# TopLevel.net
KiCad netlist of a schematic drawn in Altium Designer
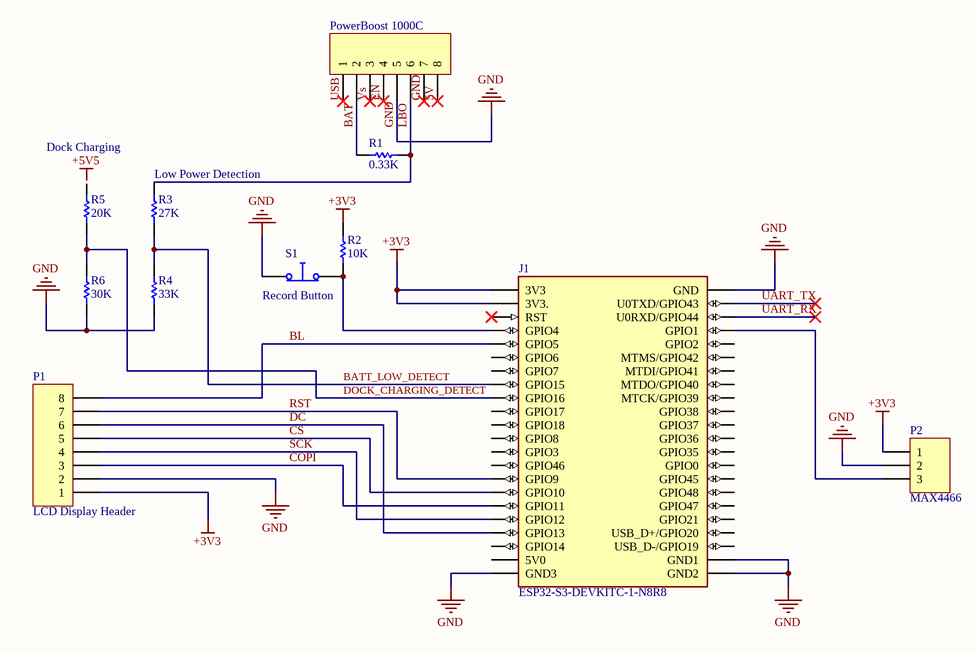
[diagram p0: TopLevel.SchDoc]

(export (version "E")
  (design (tool "Eeschema 10.0.6"))
  (components
    (comp (ref "J1")
      (value "ESP32-S3-DEVKITC-1-N8R8")
      (footprint "ESP32-S3-DEVKITC-1-N8R8")
      (fields (field (name "MF") "Espressif Systems"))
      (libsource (lib "Personal") (part "ESP32-S3-DEVKITC-1-N8R8"))
    )
    (comp (ref "P1")
      (value "LCD Display Header")
      (footprint "HDR1X8")
      (description "Header, 8-Pin")
      (fields (field (name "PUBLISHER") "Altium Limited"))
      (libsource (lib "") (part "Header 8H_1"))
    )
    (comp (ref "P2")
      (value "MAX4466")
      (footprint "HDR1X3")
      (description "Header, 3-Pin")
      (fields (field (name "PUBLISHER") "Altium Limited"))
      (libsource (lib "Personal") (part "Header 3H"))
    )
    (comp (ref "PowerBoost 1000C")
      (value "CD Display Header")
      (footprint "HDR1X8")
      (description "Header, 8-Pin")
      (fields (field (name "PUBLISHER") "Altium Limited"))
      (libsource (lib "Personal") (part "Header 8H"))
    )
    (comp (ref "R1")
      (value "0.33K")
      (description "Resistor")
      (libsource (lib "Simulation Generic Components") (part "Resistor"))
    )
    (comp (ref "R2")
      (value "10K")
      (description "Resistor")
      (libsource (lib "Simulation Generic Components") (part "Resistor"))
    )
    (comp (ref "R3")
      (value "27K")
      (description "Resistor")
      (libsource (lib "Simulation Generic Components") (part "Resistor"))
    )
    (comp (ref "R4")
      (value "33K")
      (description "Resistor")
      (libsource (lib "Simulation Generic Components") (part "Resistor"))
    )
    (comp (ref "R5")
      (value "20K")
      (description "Resistor")
      (libsource (lib "Simulation Generic Components") (part "Resistor"))
    )
    (comp (ref "R6")
      (value "30K")
      (description "Resistor")
      (libsource (lib "Simulation Generic Components") (part "Resistor"))
    )
    (comp (ref "S1")
      (value "Push Button Normally Closed")
      (libsource (lib "Simulation Generic Components") (part "Push Button NC"))
    )
  )
  (nets
    (net (code "1") (name "+3V3") (class "Default")
      (node (ref "J1") (pin "J1_1") (pinfunction "3V3_J1_1") (pintype "power_in"))
      (node (ref "J1") (pin "J1_2") (pinfunction "3V3._J1_2") (pintype "power_in"))
      (node (ref "P1") (pin "1") (pinfunction "1_1") (pintype "passive"))
      (node (ref "P2") (pin "1") (pinfunction "1_1") (pintype "passive"))
      (node (ref "R2") (pin "2") (pinfunction "2_2") (pintype "passive"))
    )
    (net (code "2") (name "+5V5") (class "Default")
      (node (ref "R5") (pin "2") (pinfunction "2_2") (pintype "passive"))
    )
    (net (code "3") (name "/5V") (class "Default")
      (node (ref "PowerBoost 1000C") (pin "8") (pinfunction "8_8") (pintype "passive+no_connect"))
    )
    (net (code "4") (name "/BAT") (class "Default")
      (node (ref "PowerBoost 1000C") (pin "2") (pinfunction "2_2") (pintype "passive"))
      (node (ref "R1") (pin "2") (pinfunction "2_2") (pintype "passive"))
    )
    (net (code "5") (name "/BATT_LOW_DETECT") (class "Default")
      (node (ref "J1") (pin "J1_8") (pinfunction "GPIO15_J1_8") (pintype "bidirectional"))
      (node (ref "R3") (pin "1") (pinfunction "1_1") (pintype "passive"))
      (node (ref "R4") (pin "2") (pinfunction "2_2") (pintype "passive"))
    )
    (net (code "6") (name "/BL") (class "Default")
      (node (ref "J1") (pin "J1_5") (pinfunction "GPIO5_J1_5") (pintype "bidirectional"))
      (node (ref "P1") (pin "8") (pinfunction "8_8") (pintype "passive"))
    )
    (net (code "7") (name "/COPI") (class "Default")
      (node (ref "J1") (pin "J1_17") (pinfunction "GPIO11_J1_17") (pintype "bidirectional"))
      (node (ref "P1") (pin "3") (pinfunction "3_3") (pintype "passive"))
    )
    (net (code "8") (name "/CS") (class "Default")
      (node (ref "J1") (pin "J1_16") (pinfunction "GPIO10_J1_16") (pintype "bidirectional"))
      (node (ref "P1") (pin "5") (pinfunction "5_5") (pintype "passive"))
    )
    (net (code "9") (name "/DC") (class "Default")
      (node (ref "J1") (pin "J1_19") (pinfunction "GPIO13_J1_19") (pintype "bidirectional"))
      (node (ref "P1") (pin "6") (pinfunction "6_6") (pintype "passive"))
    )
    (net (code "10") (name "/DOCK_CHARGING_DETECT") (class "Default")
      (node (ref "J1") (pin "J1_9") (pinfunction "GPIO16_J1_9") (pintype "bidirectional"))
      (node (ref "R5") (pin "1") (pinfunction "1_1") (pintype "passive"))
      (node (ref "R6") (pin "2") (pinfunction "2_2") (pintype "passive"))
    )
    (net (code "11") (name "/EN") (class "Default")
      (node (ref "PowerBoost 1000C") (pin "4") (pinfunction "4_4") (pintype "passive+no_connect"))
    )
    (net (code "12") (name "/LBO") (class "Default")
      (node (ref "PowerBoost 1000C") (pin "6") (pinfunction "6_6") (pintype "passive"))
      (node (ref "R1") (pin "1") (pinfunction "1_1") (pintype "passive"))
      (node (ref "R3") (pin "2") (pinfunction "2_2") (pintype "passive"))
    )
    (net (code "13") (name "/RST") (class "Default")
      (node (ref "J1") (pin "J1_15") (pinfunction "GPIO9_J1_15") (pintype "bidirectional"))
      (node (ref "P1") (pin "7") (pinfunction "7_7") (pintype "passive"))
    )
    (net (code "14") (name "/SCK") (class "Default")
      (node (ref "J1") (pin "J1_18") (pinfunction "GPIO12_J1_18") (pintype "bidirectional"))
      (node (ref "P1") (pin "4") (pinfunction "4_4") (pintype "passive"))
    )
    (net (code "15") (name "/UART_RX") (class "Default")
      (node (ref "J1") (pin "J3_3") (pinfunction "U0RXD/GPIO44_J3_3") (pintype "bidirectional+no_connect"))
    )
    (net (code "16") (name "/UART_TX") (class "Default")
      (node (ref "J1") (pin "J3_2") (pinfunction "U0TXD/GPIO43_J3_2") (pintype "bidirectional+no_connect"))
    )
    (net (code "17") (name "/USB") (class "Default")
      (node (ref "PowerBoost 1000C") (pin "1") (pinfunction "1_1") (pintype "passive+no_connect"))
    )
    (net (code "18") (name "/Vs") (class "Default")
      (node (ref "PowerBoost 1000C") (pin "3") (pinfunction "3_3") (pintype "passive+no_connect"))
    )
    (net (code "19") (name "GND") (class "Default")
      (node (ref "J1") (pin "J1_22") (pinfunction "GND3_J1_22") (pintype "power_in"))
      (node (ref "J1") (pin "J3_1") (pinfunction "GND_J3_1") (pintype "power_in"))
      (node (ref "J1") (pin "J3_21") (pinfunction "GND1_J3_21") (pintype "power_in"))
      (node (ref "J1") (pin "J3_22") (pinfunction "GND2_J3_22") (pintype "power_in"))
      (node (ref "P1") (pin "2") (pinfunction "2_2") (pintype "passive"))
      (node (ref "P2") (pin "2") (pinfunction "2_2") (pintype "passive"))
      (node (ref "PowerBoost 1000C") (pin "5") (pinfunction "5_5") (pintype "passive"))
      (node (ref "PowerBoost 1000C") (pin "7") (pinfunction "7_7") (pintype "passive"))
      (node (ref "R4") (pin "1") (pinfunction "1_1") (pintype "passive"))
      (node (ref "R6") (pin "1") (pinfunction "1_1") (pintype "passive"))
      (node (ref "S1") (pin "1") (pinfunction "1_1") (pintype "passive"))
    )
    (net (code "20") (name "Net-(J1-GPIO1)") (class "Default")
      (node (ref "J1") (pin "J3_4") (pinfunction "GPIO1_J3_4") (pintype "bidirectional"))
      (node (ref "P2") (pin "3") (pinfunction "3_3") (pintype "passive"))
    )
    (net (code "21") (name "Net-(J1-GPIO4)") (class "Default")
      (node (ref "J1") (pin "J1_4") (pinfunction "GPIO4_J1_4") (pintype "bidirectional"))
      (node (ref "R2") (pin "1") (pinfunction "1_1") (pintype "passive"))
      (node (ref "S1") (pin "2") (pinfunction "2_2") (pintype "passive"))
    )
    (net (code "22") (name "unconnected-(J1-5V0-PadJ1_21)") (class "Default")
      (node (ref "J1") (pin "J1_21") (pinfunction "5V0_J1_21") (pintype "power_in"))
    )
    (net (code "23") (name "unconnected-(J1-GPIO0-PadJ3_14)") (class "Default")
      (node (ref "J1") (pin "J3_14") (pinfunction "GPIO0_J3_14") (pintype "bidirectional"))
    )
    (net (code "24") (name "unconnected-(J1-GPIO2-PadJ3_5)") (class "Default")
      (node (ref "J1") (pin "J3_5") (pinfunction "GPIO2_J3_5") (pintype "bidirectional"))
    )
    (net (code "25") (name "unconnected-(J1-GPIO3-PadJ1_13)") (class "Default")
      (node (ref "J1") (pin "J1_13") (pinfunction "GPIO3_J1_13") (pintype "bidirectional"))
    )
    (net (code "26") (name "unconnected-(J1-GPIO6-PadJ1_6)") (class "Default")
      (node (ref "J1") (pin "J1_6") (pinfunction "GPIO6_J1_6") (pintype "bidirectional"))
    )
    (net (code "27") (name "unconnected-(J1-GPIO7-PadJ1_7)") (class "Default")
      (node (ref "J1") (pin "J1_7") (pinfunction "GPIO7_J1_7") (pintype "bidirectional"))
    )
    (net (code "28") (name "unconnected-(J1-GPIO8-PadJ1_12)") (class "Default")
      (node (ref "J1") (pin "J1_12") (pinfunction "GPIO8_J1_12") (pintype "bidirectional"))
    )
    (net (code "29") (name "unconnected-(J1-GPIO14-PadJ1_20)") (class "Default")
      (node (ref "J1") (pin "J1_20") (pinfunction "GPIO14_J1_20") (pintype "bidirectional"))
    )
    (net (code "30") (name "unconnected-(J1-GPIO17-PadJ1_10)") (class "Default")
      (node (ref "J1") (pin "J1_10") (pinfunction "GPIO17_J1_10") (pintype "bidirectional"))
    )
    (net (code "31") (name "unconnected-(J1-GPIO18-PadJ1_11)") (class "Default")
      (node (ref "J1") (pin "J1_11") (pinfunction "GPIO18_J1_11") (pintype "bidirectional"))
    )
    (net (code "32") (name "unconnected-(J1-GPIO21-PadJ3_18)") (class "Default")
      (node (ref "J1") (pin "J3_18") (pinfunction "GPIO21_J3_18") (pintype "bidirectional"))
    )
    (net (code "33") (name "unconnected-(J1-GPIO35-PadJ3_13)") (class "Default")
      (node (ref "J1") (pin "J3_13") (pinfunction "GPIO35_J3_13") (pintype "bidirectional"))
    )
    (net (code "34") (name "unconnected-(J1-GPIO36-PadJ3_12)") (class "Default")
      (node (ref "J1") (pin "J3_12") (pinfunction "GPIO36_J3_12") (pintype "bidirectional"))
    )
    (net (code "35") (name "unconnected-(J1-GPIO37-PadJ3_11)") (class "Default")
      (node (ref "J1") (pin "J3_11") (pinfunction "GPIO37_J3_11") (pintype "bidirectional"))
    )
    (net (code "36") (name "unconnected-(J1-GPIO38-PadJ3_10)") (class "Default")
      (node (ref "J1") (pin "J3_10") (pinfunction "GPIO38_J3_10") (pintype "bidirectional"))
    )
    (net (code "37") (name "unconnected-(J1-GPIO45-PadJ3_15)") (class "Default")
      (node (ref "J1") (pin "J3_15") (pinfunction "GPIO45_J3_15") (pintype "bidirectional"))
    )
    (net (code "38") (name "unconnected-(J1-GPIO46-PadJ1_14)") (class "Default")
      (node (ref "J1") (pin "J1_14") (pinfunction "GPIO46_J1_14") (pintype "bidirectional"))
    )
    (net (code "39") (name "unconnected-(J1-GPIO47-PadJ3_17)") (class "Default")
      (node (ref "J1") (pin "J3_17") (pinfunction "GPIO47_J3_17") (pintype "bidirectional"))
    )
    (net (code "40") (name "unconnected-(J1-GPIO48-PadJ3_16)") (class "Default")
      (node (ref "J1") (pin "J3_16") (pinfunction "GPIO48_J3_16") (pintype "bidirectional"))
    )
    (net (code "41") (name "unconnected-(J1-MTCK{slash}GPIO39-PadJ3_9)") (class "Default")
      (node (ref "J1") (pin "J3_9") (pinfunction "MTCK/GPIO39_J3_9") (pintype "bidirectional"))
    )
    (net (code "42") (name "unconnected-(J1-MTDI{slash}GPIO41-PadJ3_7)") (class "Default")
      (node (ref "J1") (pin "J3_7") (pinfunction "MTDI/GPIO41_J3_7") (pintype "bidirectional"))
    )
    (net (code "43") (name "unconnected-(J1-MTDO{slash}GPIO40-PadJ3_8)") (class "Default")
      (node (ref "J1") (pin "J3_8") (pinfunction "MTDO/GPIO40_J3_8") (pintype "bidirectional"))
    )
    (net (code "44") (name "unconnected-(J1-MTMS{slash}GPIO42-PadJ3_6)") (class "Default")
      (node (ref "J1") (pin "J3_6") (pinfunction "MTMS/GPIO42_J3_6") (pintype "bidirectional"))
    )
    (net (code "45") (name "unconnected-(J1-RST-PadJ1_3)") (class "Default")
      (node (ref "J1") (pin "J1_3") (pinfunction "RST_J1_3") (pintype "input+no_connect"))
    )
    (net (code "46") (name "unconnected-(J1-USB_D+{slash}GPIO20-PadJ3_19)") (class "Default")
      (node (ref "J1") (pin "J3_19") (pinfunction "USB_D+/GPIO20_J3_19") (pintype "bidirectional"))
    )
    (net (code "47") (name "unconnected-(J1-USB_D-{slash}GPIO19-PadJ3_20)") (class "Default")
      (node (ref "J1") (pin "J3_20") (pinfunction "USB_D-/GPIO19_J3_20") (pintype "bidirectional"))
    )
  )
)
